# STeaMi-FP8-Display_et_LED_statuts.net
KiCad netlist of a schematic drawn in Altium Designer
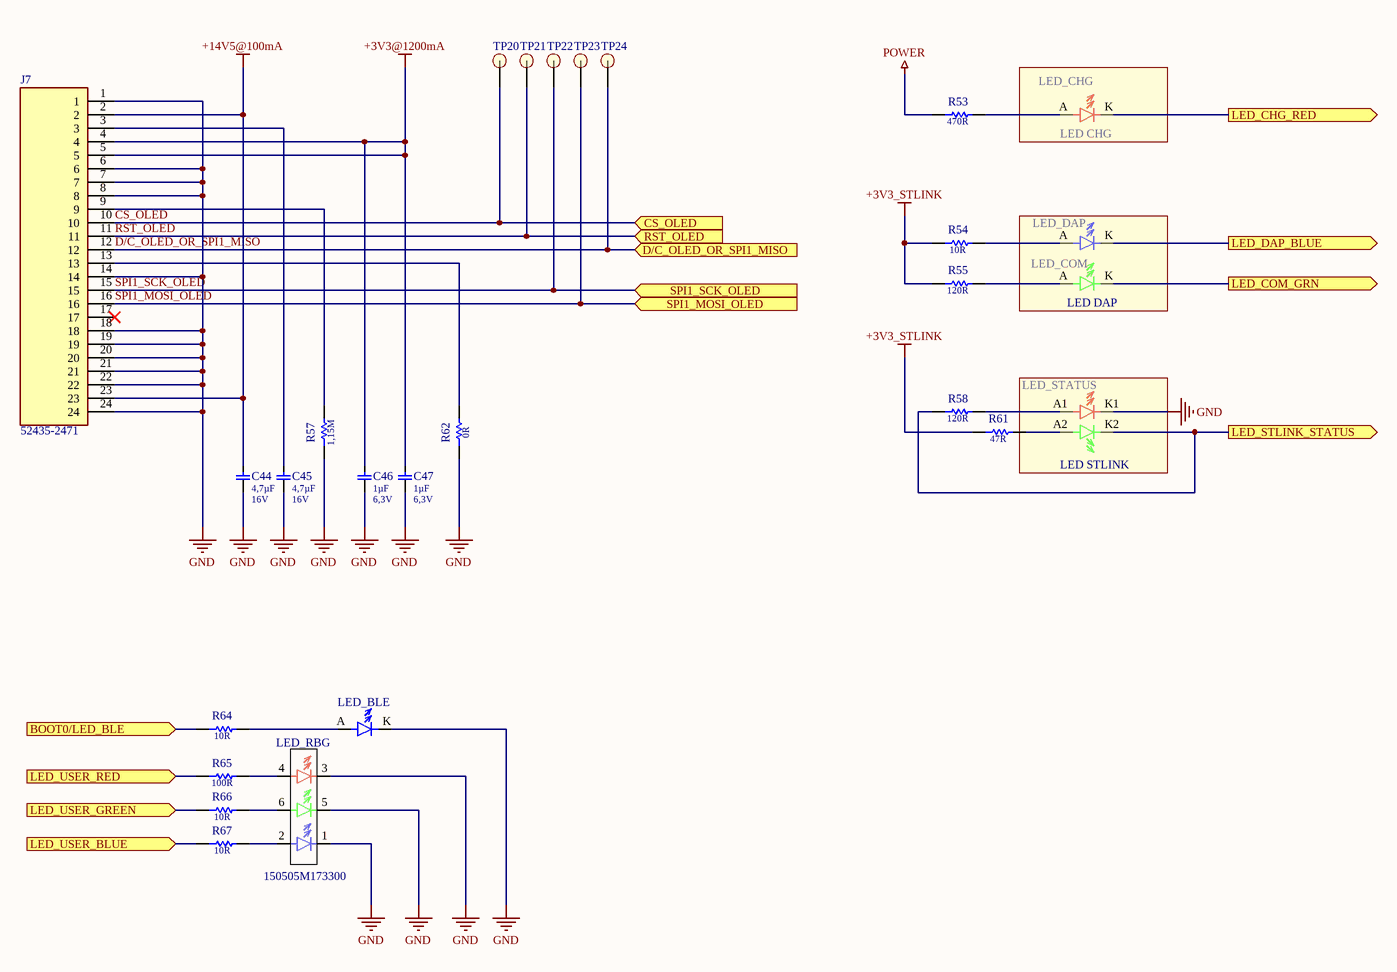
[diagram p0: STeaMi-FP8-Display_et_LED_statuts.SchDoc]

(export (version "E")
  (design (tool "Eeschema 10.0.6"))
  (components
    (comp (ref "C44")
      (value "~")
      (footprint "0402-CAP")
      (description "CAP CER 4,7µF 16V X5R 0402")
      (fields
        (field (name "MANUFACTURER") "Kyocera AVX")
        (field (name "MANUFACTURER PART NUMBER") "0402YD475MAT2A")
        (field (name "CAPACITANCE") "4,7µF")
        (field (name "VOLTAGE") "16V")
        (field (name "CREATED BY") "EAG")
        (field (name "CHECKED BY") "*")
      )
      (libsource (lib "ComponentDB") (part "CAP_SYMBOL"))
    )
    (comp (ref "C45")
      (value "~")
      (footprint "0402-CAP")
      (description "CAP CER 4,7µF 16V X5R 0402")
      (fields
        (field (name "MANUFACTURER") "Kyocera AVX")
        (field (name "MANUFACTURER PART NUMBER") "0402YD475MAT2A")
        (field (name "CAPACITANCE") "4,7µF")
        (field (name "VOLTAGE") "16V")
        (field (name "CREATED BY") "EAG")
        (field (name "CHECKED BY") "*")
      )
      (libsource (lib "ComponentDB") (part "CAP_SYMBOL"))
    )
    (comp (ref "C46")
      (value "~")
      (footprint "0402-CAP")
      (description "CAP CER 1µF 6,3V X5R 0402")
      (fields
        (field (name "MANUFACTURER") "Taiyo Yuden")
        (field (name "MANUFACTURER PART NUMBER") "JMK105BJ105KV-F")
        (field (name "CAPACITANCE") "1µF")
        (field (name "VOLTAGE") "6,3V")
        (field (name "CREATED BY") "EAG")
        (field (name "CHECKED BY") "*")
      )
      (libsource (lib "ComponentDB") (part "CAP_SYMBOL"))
    )
    (comp (ref "C47")
      (value "~")
      (footprint "0402-CAP")
      (description "CAP CER 1µF 6,3V X5R 0402")
      (fields
        (field (name "MANUFACTURER") "Taiyo Yuden")
        (field (name "MANUFACTURER PART NUMBER") "JMK105BJ105KV-F")
        (field (name "CAPACITANCE") "1µF")
        (field (name "VOLTAGE") "6,3V")
        (field (name "CREATED BY") "EAG")
        (field (name "CHECKED BY") "*")
      )
      (libsource (lib "ComponentDB") (part "CAP_SYMBOL"))
    )
    (comp (ref "J7")
      (value "~")
      (footprint "52435-2471")
      (description "FFC/FPC connector 0,50 Pitch Slider Right angle TOP Contact")
      (fields
        (field (name "MANUFACTURER") "Molex")
        (field (name "MANUFACTURER PART NUMBER") "52435-2471")
        (field (name "PART NUMBER") "52435-2471")
        (field (name "CHECKED BY") "*")
        (field (name "CREATED BY") "EAG")
      )
      (libsource (lib "ComponentDB") (part "52435-2471"))
    )
    (comp (ref "LED_BLE")
      (value "~")
      (footprint "APTD1608LZGCK-B")
      (description "DEL standard - CMS WL-SMCW SMDMono TpVw Waterclr 0603 Blue")
      (fields
        (field (name "MANUFACTURER") "WURTH")
        (field (name "MANUFACTURER PART NUMBER") "150060BS75000")
        (field (name "CREATED BY") "EAG")
      )
      (libsource (lib "ComponentDB") (part "LED_BLUE_SYMBOL"))
    )
    (comp (ref "LED_CHG")
      (value "~")
      (footprint "APTD1608LZGCK")
      (description "DEL standard - CMS WL-SMCW SMDMono TpVw Waterclr 0603 RED")
      (fields
        (field (name "MANUFACTURER") "WURTH")
        (field (name "MANUFACTURER PART NUMBER") "150060RS75000")
        (field (name "CREATED BY") "EAG")
      )
      (libsource (lib "ComponentDB") (part "LED_RED_SYMBOL"))
    )
    (comp (ref "LED_COM")
      (value "~")
      (footprint "APTD1608LZGCK")
      (description "LED GREEN 2V 20mA 0603 SMD")
      (fields
        (field (name "MANUFACTURER") "WURTH")
        (field (name "MANUFACTURER PART NUMBER") "150060VS75000")
        (field (name "CREATED BY") "EAG")
      )
      (libsource (lib "ComponentDB") (part "LED_GREEN_SYMBOL"))
    )
    (comp (ref "LED_DAP")
      (value "~")
      (footprint "APTD1608LZGCK")
      (description "DEL standard - CMS WL-SMCW SMDMono TpVw Waterclr 0603 Blue")
      (fields
        (field (name "MANUFACTURER") "WURTH")
        (field (name "MANUFACTURER PART NUMBER") "150060BS75000")
        (field (name "CREATED BY") "EAG")
      )
      (libsource (lib "ComponentDB") (part "LED_BLUE_SYMBOL"))
    )
    (comp (ref "LED_RBG")
      (value "~")
      (footprint "150505M173300")
      (description "DEL standard - CMS WL-SFTW SMD TOP SMD 5050 RGB")
      (fields
        (field (name "MANUFACTURER") "WURTH")
        (field (name "MANUFACTURER PART NUMBER") "150505M173300")
        (field (name "PART NUMBER") "150505M173300")
        (field (name "CREATED BY") "EAG")
      )
      (libsource (lib "ComponentDB") (part "LED_RBG_6_PIN"))
    )
    (comp (ref "LED_STATUS")
      (value "~")
      (footprint "KPHBM2012QBDCGKC")
      (description "LED BI Green Red 2mm x 1,25mm SMD")
      (fields
        (field (name "MANUFACTURER") "Kingbright")
        (field (name "MANUFACTURER PART NUMBER") "APHBM2012LSURKZGKC")
        (field (name "CREATED BY") "EAG")
      )
      (libsource (lib "ComponentDB") (part "BICOLOR_SYMBOL"))
    )
    (comp (ref "R53")
      (value "~")
      (footprint "RESC1005X40N_0402")
      (description "RES CMS 470R5%-0,1W-0402 ±200ppm/°C")
      (fields
        (field (name "MANUFACTURER") "Panasonic")
        (field (name "MANUFACTURER PART NUMBER") "ERJ-2GEJ471X")
        (field (name "RESISTANCE") "470R")
        (field (name "CREATED BY") "EAG")
      )
      (libsource (lib "ComponentDB") (part "RES_SYMBOL"))
    )
    (comp (ref "R54")
      (value "~")
      (footprint "RESC1005X40N_0402")
      (description "RES CMS 10R1%-0,0625W-0402 ±200ppm/°C")
      (fields
        (field (name "MANUFACTURER") "Yageo")
        (field (name "MANUFACTURER PART NUMBER") "RC0402FR-1010RL")
        (field (name "RESISTANCE") "10R")
        (field (name "CREATED BY") "EAG")
      )
      (libsource (lib "ComponentDB") (part "RES_SYMBOL"))
    )
    (comp (ref "R55")
      (value "~")
      (footprint "RESC1005X40N_0402")
      (description "RES CMS 120R1%-0,0625W-0402 ±200ppm/°C")
      (fields
        (field (name "MANUFACTURER") "Yageo")
        (field (name "MANUFACTURER PART NUMBER") "AC0402FR-07120RL")
        (field (name "RESISTANCE") "120R")
        (field (name "CREATED BY") "EAG")
      )
      (libsource (lib "ComponentDB") (part "RES_SYMBOL"))
    )
    (comp (ref "R57")
      (value "~")
      (footprint "RESC1005X40N_0402")
      (description "RES CMS 1,15M1%-0,1W-0402 ±0ppm/°C")
      (fields
        (field (name "MANUFACTURER") "KOA Speer")
        (field (name "MANUFACTURER PART NUMBER") "RK73H1ETTP1154F")
        (field (name "RESISTANCE") "1,15M")
        (field (name "CREATED BY") "EAG")
      )
      (libsource (lib "ComponentDB") (part "RES_SYMBOL"))
    )
    (comp (ref "R58")
      (value "~")
      (footprint "RESC1005X40N_0402")
      (description "RES CMS 120R1%-0,0625W-0402 ±200ppm/°C")
      (fields
        (field (name "MANUFACTURER") "Yageo")
        (field (name "MANUFACTURER PART NUMBER") "AC0402FR-07120RL")
        (field (name "RESISTANCE") "120R")
        (field (name "CREATED BY") "EAG")
      )
      (libsource (lib "ComponentDB") (part "RES_SYMBOL"))
    )
    (comp (ref "R61")
      (value "~")
      (footprint "RESC1005X40N_0402")
      (description "RES CMS 47R1%-0,0625W-0402 ±100ppm/°C")
      (fields
        (field (name "MANUFACTURER") "Yageo")
        (field (name "MANUFACTURER PART NUMBER") "RC0402FR-0747RL")
        (field (name "RESISTANCE") "47R")
        (field (name "CREATED BY") "EAG")
      )
      (libsource (lib "ComponentDB") (part "RES_SYMBOL"))
    )
    (comp (ref "R62")
      (value "~")
      (footprint "RESC1005X40N_0402")
      (description "RES CMS 0R5%-0,0625W-0402")
      (fields
        (field (name "MANUFACTURER") "Yageo")
        (field (name "MANUFACTURER PART NUMBER") "RC0402JR-100RL")
        (field (name "RESISTANCE") "0R")
        (field (name "CREATED BY") "EAG")
      )
      (libsource (lib "ComponentDB") (part "RES_SYMBOL"))
    )
    (comp (ref "R64")
      (value "~")
      (footprint "RESC1005X40N_0402")
      (description "RES CMS 10R1%-0,0625W-0402 ±200ppm/°C")
      (fields
        (field (name "MANUFACTURER") "Yageo")
        (field (name "MANUFACTURER PART NUMBER") "RC0402FR-1010RL")
        (field (name "RESISTANCE") "10R")
        (field (name "CREATED BY") "EAG")
      )
      (libsource (lib "ComponentDB") (part "RES_SYMBOL"))
    )
    (comp (ref "R65")
      (value "~")
      (footprint "RESC1005X40N_0402")
      (description "RES CMS 100R5%-0,0625W-0402 ±100ppm/°C")
      (fields
        (field (name "MANUFACTURER") "Yageo")
        (field (name "MANUFACTURER PART NUMBER") "RC0402JR-07100RL")
        (field (name "RESISTANCE") "100R")
        (field (name "CREATED BY") "EAG")
      )
      (libsource (lib "ComponentDB") (part "RES_SYMBOL"))
    )
    (comp (ref "R66")
      (value "~")
      (footprint "RESC1005X40N_0402")
      (description "RES CMS 10R1%-0,0625W-0402 ±200ppm/°C")
      (fields
        (field (name "MANUFACTURER") "Yageo")
        (field (name "MANUFACTURER PART NUMBER") "RC0402FR-1010RL")
        (field (name "RESISTANCE") "10R")
        (field (name "CREATED BY") "EAG")
      )
      (libsource (lib "ComponentDB") (part "RES_SYMBOL"))
    )
    (comp (ref "R67")
      (value "~")
      (footprint "RESC1005X40N_0402")
      (description "RES CMS 10R1%-0,0625W-0402 ±200ppm/°C")
      (fields
        (field (name "MANUFACTURER") "Yageo")
        (field (name "MANUFACTURER PART NUMBER") "RC0402FR-1010RL")
        (field (name "RESISTANCE") "10R")
        (field (name "CREATED BY") "EAG")
      )
      (libsource (lib "ComponentDB") (part "RES_SYMBOL"))
    )
    (comp (ref "TP20")
      (value "PAD")
      (footprint "Testpoint 1mm")
      (description "TESTPOINTPAD")
      (fields
        (field (name "MANUFACTURER") "Smartembed")
        (field (name "MANUFACTURER PART NUMBER") "TESTPOINT")
        (field (name "CREATED BY") "EAG")
      )
      (libsource (lib "ComponentDB") (part "TESTPOINT"))
    )
    (comp (ref "TP21")
      (value "PAD")
      (footprint "Testpoint 1mm")
      (description "TESTPOINTPAD")
      (fields
        (field (name "MANUFACTURER") "Smartembed")
        (field (name "MANUFACTURER PART NUMBER") "TESTPOINT")
        (field (name "CREATED BY") "EAG")
      )
      (libsource (lib "ComponentDB") (part "TESTPOINT"))
    )
    (comp (ref "TP22")
      (value "SCK1")
      (footprint "Testpoint 1mm")
      (description "TESTPOINTPAD")
      (fields
        (field (name "MANUFACTURER") "Smartembed")
        (field (name "MANUFACTURER PART NUMBER") "TESTPOINT")
        (field (name "CREATED BY") "EAG")
      )
      (libsource (lib "ComponentDB") (part "TESTPOINT"))
    )
    (comp (ref "TP23")
      (value "MOSI1")
      (footprint "Testpoint 1mm")
      (description "TESTPOINTPAD")
      (fields
        (field (name "MANUFACTURER") "Smartembed")
        (field (name "MANUFACTURER PART NUMBER") "TESTPOINT")
        (field (name "CREATED BY") "EAG")
      )
      (libsource (lib "ComponentDB") (part "TESTPOINT"))
    )
    (comp (ref "TP24")
      (value "PAD")
      (footprint "Testpoint 1mm")
      (description "TESTPOINTPAD")
      (fields
        (field (name "MANUFACTURER") "Smartembed")
        (field (name "MANUFACTURER PART NUMBER") "TESTPOINT")
        (field (name "CREATED BY") "EAG")
      )
      (libsource (lib "ComponentDB") (part "TESTPOINT"))
    )
  )
  (nets
    (net (code "1") (name "+3V3@1200mA") (class "Default")
      (node (ref "C46") (pin "2") (pinfunction "2_2") (pintype "passive"))
      (node (ref "C47") (pin "2") (pinfunction "2_2") (pintype "passive"))
      (node (ref "J7") (pin "4") (pinfunction "4_4") (pintype "passive"))
      (node (ref "J7") (pin "5") (pinfunction "5_5") (pintype "passive"))
    )
    (net (code "2") (name "+3V3_STLINK") (class "Default")
      (node (ref "R54") (pin "1") (pinfunction "1_1") (pintype "passive"))
      (node (ref "R55") (pin "1") (pinfunction "1_1") (pintype "passive"))
      (node (ref "R61") (pin "1") (pinfunction "1_1") (pintype "passive"))
    )
    (net (code "3") (name "+14V5@100mA") (class "Default")
      (node (ref "C44") (pin "2") (pinfunction "2_2") (pintype "passive"))
      (node (ref "J7") (pin "2") (pinfunction "2_2") (pintype "passive"))
      (node (ref "J7") (pin "23") (pinfunction "23_23") (pintype "passive"))
    )
    (net (code "4") (name "/BOOT0{slash}LED_BLE") (class "Default")
      (node (ref "R64") (pin "1") (pinfunction "1_1") (pintype "passive"))
    )
    (net (code "5") (name "/CS_OLED") (class "Default")
      (node (ref "J7") (pin "10") (pinfunction "10_10") (pintype "passive"))
      (node (ref "TP20") (pin "1") (pinfunction "1_1") (pintype "passive"))
    )
    (net (code "6") (name "/D{slash}C_OLED_OR_SPI1_MISO") (class "Default")
      (node (ref "J7") (pin "12") (pinfunction "12_12") (pintype "passive"))
      (node (ref "TP24") (pin "1") (pinfunction "1_1") (pintype "passive"))
    )
    (net (code "7") (name "/LED_CHG_RED") (class "Default")
      (node (ref "LED_CHG") (pin "K") (pinfunction "K_K") (pintype "passive"))
    )
    (net (code "8") (name "/LED_COM_GRN") (class "Default")
      (node (ref "LED_COM") (pin "K") (pinfunction "K_K") (pintype "passive"))
    )
    (net (code "9") (name "/LED_DAP_BLUE") (class "Default")
      (node (ref "LED_DAP") (pin "K") (pinfunction "K_K") (pintype "passive"))
    )
    (net (code "10") (name "/LED_STLINK_STATUS") (class "Default")
      (node (ref "LED_STATUS") (pin "K2") (pinfunction "K2_K2") (pintype "passive"))
      (node (ref "R58") (pin "1") (pinfunction "1_1") (pintype "passive"))
    )
    (net (code "11") (name "/LED_USER_BLUE") (class "Default")
      (node (ref "R67") (pin "1") (pinfunction "1_1") (pintype "passive"))
    )
    (net (code "12") (name "/LED_USER_GREEN") (class "Default")
      (node (ref "R66") (pin "1") (pinfunction "1_1") (pintype "passive"))
    )
    (net (code "13") (name "/LED_USER_RED") (class "Default")
      (node (ref "R65") (pin "1") (pinfunction "1_1") (pintype "passive"))
    )
    (net (code "14") (name "/RST_OLED") (class "Default")
      (node (ref "J7") (pin "11") (pinfunction "11_11") (pintype "passive"))
      (node (ref "TP21") (pin "1") (pinfunction "1_1") (pintype "passive"))
    )
    (net (code "15") (name "/SPI1_MOSI_OLED") (class "Default")
      (node (ref "J7") (pin "16") (pinfunction "16_16") (pintype "passive"))
      (node (ref "TP23") (pin "1") (pinfunction "1_1") (pintype "passive"))
    )
    (net (code "16") (name "/SPI1_SCK_OLED") (class "Default")
      (node (ref "J7") (pin "15") (pinfunction "15_15") (pintype "passive"))
      (node (ref "TP22") (pin "1") (pinfunction "1_1") (pintype "passive"))
    )
    (net (code "17") (name "GND") (class "Default")
      (node (ref "C44") (pin "1") (pinfunction "1_1") (pintype "passive"))
      (node (ref "C45") (pin "1") (pinfunction "1_1") (pintype "passive"))
      (node (ref "C46") (pin "1") (pinfunction "1_1") (pintype "passive"))
      (node (ref "C47") (pin "1") (pinfunction "1_1") (pintype "passive"))
      (node (ref "J7") (pin "1") (pinfunction "1_1") (pintype "passive"))
      (node (ref "J7") (pin "14") (pinfunction "14_14") (pintype "passive"))
      (node (ref "J7") (pin "18") (pinfunction "18_18") (pintype "passive"))
      (node (ref "J7") (pin "19") (pinfunction "19_19") (pintype "passive"))
      (node (ref "J7") (pin "20") (pinfunction "20_20") (pintype "passive"))
      (node (ref "J7") (pin "21") (pinfunction "21_21") (pintype "passive"))
      (node (ref "J7") (pin "22") (pinfunction "22_22") (pintype "passive"))
      (node (ref "J7") (pin "24") (pinfunction "24_24") (pintype "passive"))
      (node (ref "J7") (pin "6") (pinfunction "6_6") (pintype "passive"))
      (node (ref "J7") (pin "7") (pinfunction "7_7") (pintype "passive"))
      (node (ref "J7") (pin "8") (pinfunction "8_8") (pintype "passive"))
      (node (ref "LED_BLE") (pin "K") (pinfunction "K_K") (pintype "passive"))
      (node (ref "LED_RBG") (pin "1") (pinfunction "1_1") (pintype "passive"))
      (node (ref "LED_RBG") (pin "3") (pinfunction "3_3") (pintype "passive"))
      (node (ref "LED_RBG") (pin "5") (pinfunction "5_5") (pintype "passive"))
      (node (ref "LED_STATUS") (pin "K1") (pinfunction "K1_K1") (pintype "passive"))
      (node (ref "R57") (pin "1") (pinfunction "1_1") (pintype "passive"))
      (node (ref "R62") (pin "1") (pinfunction "1_1") (pintype "passive"))
    )
    (net (code "18") (name "Net-(C45-Pad2)") (class "Default")
      (node (ref "C45") (pin "2") (pinfunction "2_2") (pintype "passive"))
      (node (ref "J7") (pin "3") (pinfunction "3_3") (pintype "passive"))
    )
    (net (code "19") (name "Net-(J7-Pad9)") (class "Default")
      (node (ref "J7") (pin "9") (pinfunction "9_9") (pintype "passive"))
      (node (ref "R57") (pin "2") (pinfunction "2_2") (pintype "passive"))
    )
    (net (code "20") (name "Net-(J7-Pad13)") (class "Default")
      (node (ref "J7") (pin "13") (pinfunction "13_13") (pintype "passive"))
      (node (ref "R62") (pin "2") (pinfunction "2_2") (pintype "passive"))
    )
    (net (code "21") (name "Net-(LED_BLE-PadA)") (class "Default")
      (node (ref "LED_BLE") (pin "A") (pinfunction "A_A") (pintype "passive"))
      (node (ref "R64") (pin "2") (pinfunction "2_2") (pintype "passive"))
    )
    (net (code "22") (name "Net-(LED_CHG-PadA)") (class "Default")
      (node (ref "LED_CHG") (pin "A") (pinfunction "A_A") (pintype "passive"))
      (node (ref "R53") (pin "2") (pinfunction "2_2") (pintype "passive"))
    )
    (net (code "23") (name "Net-(LED_COM-PadA)") (class "Default")
      (node (ref "LED_COM") (pin "A") (pinfunction "A_A") (pintype "passive"))
      (node (ref "R55") (pin "2") (pinfunction "2_2") (pintype "passive"))
    )
    (net (code "24") (name "Net-(LED_DAP-PadA)") (class "Default")
      (node (ref "LED_DAP") (pin "A") (pinfunction "A_A") (pintype "passive"))
      (node (ref "R54") (pin "2") (pinfunction "2_2") (pintype "passive"))
    )
    (net (code "25") (name "Net-(LED_RBG-Pad2)") (class "Default")
      (node (ref "LED_RBG") (pin "2") (pinfunction "2_2") (pintype "passive"))
      (node (ref "R67") (pin "2") (pinfunction "2_2") (pintype "passive"))
    )
    (net (code "26") (name "Net-(LED_RBG-Pad4)") (class "Default")
      (node (ref "LED_RBG") (pin "4") (pinfunction "4_4") (pintype "passive"))
      (node (ref "R65") (pin "2") (pinfunction "2_2") (pintype "passive"))
    )
    (net (code "27") (name "Net-(LED_RBG-Pad6)") (class "Default")
      (node (ref "LED_RBG") (pin "6") (pinfunction "6_6") (pintype "passive"))
      (node (ref "R66") (pin "2") (pinfunction "2_2") (pintype "passive"))
    )
    (net (code "28") (name "Net-(LED_STATUS-PadA1)") (class "Default")
      (node (ref "LED_STATUS") (pin "A1") (pinfunction "A1_A1") (pintype "passive"))
      (node (ref "R58") (pin "2") (pinfunction "2_2") (pintype "passive"))
    )
    (net (code "29") (name "Net-(LED_STATUS-PadA2)") (class "Default")
      (node (ref "LED_STATUS") (pin "A2") (pinfunction "A2_A2") (pintype "passive"))
      (node (ref "R61") (pin "2") (pinfunction "2_2") (pintype "passive"))
    )
    (net (code "30") (name "POWER") (class "Default")
      (node (ref "R53") (pin "1") (pinfunction "1_1") (pintype "passive"))
    )
    (net (code "31") (name "unconnected-(J7-Pad17)") (class "Default")
      (node (ref "J7") (pin "17") (pinfunction "17_17") (pintype "passive+no_connect"))
    )
  )
)
